# adc-dac.net
KiCad netlist of a schematic drawn in Altium Designer
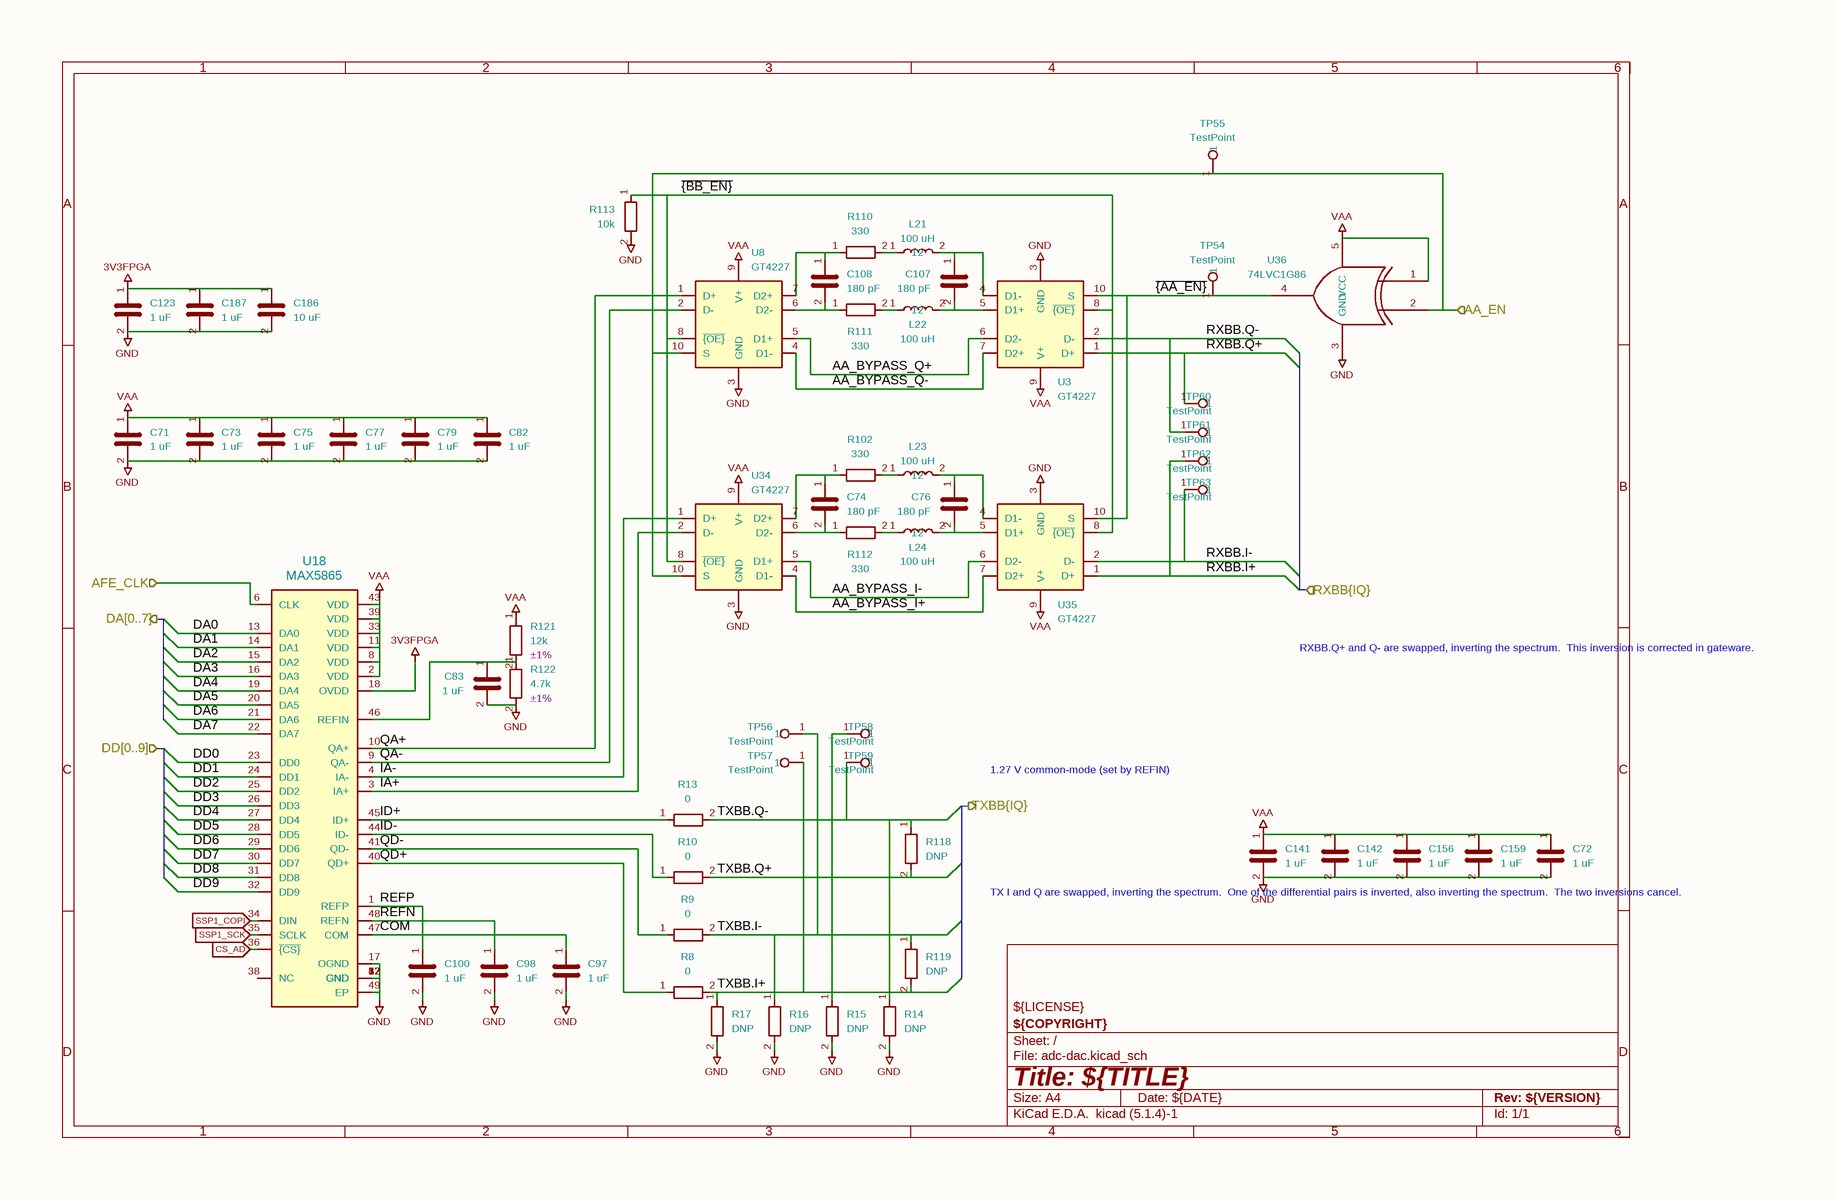
[diagram p0: adc-dac.SchDoc]

(export (version "E")
  (design (tool "Eeschema 10.0.6"))
  (components
    (comp (ref "C71")
      (value "1 uF")
      (footprint "C_0201_0603Metric")
      (description "CAP CER 1UF 10V X5R 0201")
      (fields (field (name "MANUFACTURER") "Murata") (field (name "PART NUMBER") "GRM033R61A105ME44D"))
      (libsource (lib "Device") (part "C"))
    )
    (comp (ref "C72")
      (value "1 uF")
      (footprint "C_0201_0603Metric")
      (description "CAP CER 1UF 10V X5R 0201")
      (fields (field (name "MANUFACTURER") "Murata") (field (name "PART NUMBER") "GRM033R61A105ME44D"))
      (libsource (lib "Device") (part "C"))
    )
    (comp (ref "C73")
      (value "1 uF")
      (footprint "C_0201_0603Metric")
      (description "CAP CER 1UF 10V X5R 0201")
      (fields (field (name "MANUFACTURER") "Murata") (field (name "PART NUMBER") "GRM033R61A105ME44D"))
      (libsource (lib "Device") (part "C"))
    )
    (comp (ref "C74")
      (value "180 pF")
      (footprint "C_0201_0603Metric")
      (description "CAP CER 180PF 50V C0G/NP0 0201")
      (fields (field (name "MANUFACTURER") "Murata") (field (name "PART NUMBER") "GRM0335C1H181JA01D"))
      (libsource (lib "Device") (part "C"))
    )
    (comp (ref "C75")
      (value "1 uF")
      (footprint "C_0201_0603Metric")
      (description "CAP CER 1UF 10V X5R 0201")
      (fields (field (name "MANUFACTURER") "Murata") (field (name "PART NUMBER") "GRM033R61A105ME44D"))
      (libsource (lib "Device") (part "C"))
    )
    (comp (ref "C76")
      (value "180 pF")
      (footprint "C_0201_0603Metric")
      (description "CAP CER 180PF 50V C0G/NP0 0201")
      (fields (field (name "MANUFACTURER") "Murata") (field (name "PART NUMBER") "GRM0335C1H181JA01D"))
      (libsource (lib "Device") (part "C"))
    )
    (comp (ref "C77")
      (value "1 uF")
      (footprint "C_0201_0603Metric")
      (description "CAP CER 1UF 10V X5R 0201")
      (fields (field (name "MANUFACTURER") "Murata") (field (name "PART NUMBER") "GRM033R61A105ME44D"))
      (libsource (lib "Device") (part "C"))
    )
    (comp (ref "C79")
      (value "1 uF")
      (footprint "C_0201_0603Metric")
      (description "CAP CER 1UF 10V X5R 0201")
      (fields (field (name "MANUFACTURER") "Murata") (field (name "PART NUMBER") "GRM033R61A105ME44D"))
      (libsource (lib "Device") (part "C"))
    )
    (comp (ref "C82")
      (value "1 uF")
      (footprint "C_0201_0603Metric")
      (description "CAP CER 1UF 10V X5R 0201")
      (fields (field (name "MANUFACTURER") "Murata") (field (name "PART NUMBER") "GRM033R61A105ME44D"))
      (libsource (lib "Device") (part "C"))
    )
    (comp (ref "C83")
      (value "1 uF")
      (footprint "C_0201_0603Metric")
      (description "CAP CER 1UF 10V X5R 0201")
      (fields (field (name "MANUFACTURER") "Murata") (field (name "PART NUMBER") "GRM033R61A105ME44D"))
      (libsource (lib "Device") (part "C"))
    )
    (comp (ref "C97")
      (value "1 uF")
      (footprint "C_0201_0603Metric")
      (description "CAP CER 1UF 10V X5R 0201")
      (fields (field (name "MANUFACTURER") "Murata") (field (name "PART NUMBER") "GRM033R61A105ME44D"))
      (libsource (lib "Device") (part "C"))
    )
    (comp (ref "C98")
      (value "1 uF")
      (footprint "C_0201_0603Metric")
      (description "CAP CER 1UF 10V X5R 0201")
      (fields (field (name "MANUFACTURER") "Murata") (field (name "PART NUMBER") "GRM033R61A105ME44D"))
      (libsource (lib "Device") (part "C"))
    )
    (comp (ref "C100")
      (value "1 uF")
      (footprint "C_0201_0603Metric")
      (description "CAP CER 1UF 10V X5R 0201")
      (fields (field (name "MANUFACTURER") "Murata") (field (name "PART NUMBER") "GRM033R61A105ME44D"))
      (libsource (lib "Device") (part "C"))
    )
    (comp (ref "C107")
      (value "180 pF")
      (footprint "C_0201_0603Metric")
      (description "CAP CER 180PF 50V C0G/NP0 0201")
      (fields (field (name "MANUFACTURER") "Murata") (field (name "PART NUMBER") "GRM0335C1H181JA01D"))
      (libsource (lib "Device") (part "C"))
    )
    (comp (ref "C108")
      (value "180 pF")
      (footprint "C_0201_0603Metric")
      (description "CAP CER 180PF 50V C0G/NP0 0201")
      (fields (field (name "MANUFACTURER") "Murata") (field (name "PART NUMBER") "GRM0335C1H181JA01D"))
      (libsource (lib "Device") (part "C"))
    )
    (comp (ref "C123")
      (value "1 uF")
      (footprint "C_0201_0603Metric")
      (description "CAP CER 1UF 10V X5R 0201")
      (fields (field (name "MANUFACTURER") "Murata") (field (name "PART NUMBER") "GRM033R61A105ME44D"))
      (libsource (lib "Device") (part "C"))
    )
    (comp (ref "C141")
      (value "1 uF")
      (footprint "C_0201_0603Metric")
      (description "CAP CER 1UF 10V X5R 0201")
      (fields (field (name "MANUFACTURER") "Murata") (field (name "PART NUMBER") "GRM033R61A105ME44D"))
      (libsource (lib "Device") (part "C"))
    )
    (comp (ref "C142")
      (value "1 uF")
      (footprint "C_0201_0603Metric")
      (description "CAP CER 1UF 10V X5R 0201")
      (fields (field (name "MANUFACTURER") "Murata") (field (name "PART NUMBER") "GRM033R61A105ME44D"))
      (libsource (lib "Device") (part "C"))
    )
    (comp (ref "C156")
      (value "1 uF")
      (footprint "C_0201_0603Metric")
      (description "CAP CER 1UF 10V X5R 0201")
      (fields (field (name "MANUFACTURER") "Murata") (field (name "PART NUMBER") "GRM033R61A105ME44D"))
      (libsource (lib "Device") (part "C"))
    )
    (comp (ref "C159")
      (value "1 uF")
      (footprint "C_0201_0603Metric")
      (description "CAP CER 1UF 10V X5R 0201")
      (fields (field (name "MANUFACTURER") "Murata") (field (name "PART NUMBER") "GRM033R61A105ME44D"))
      (libsource (lib "Device") (part "C"))
    )
    (comp (ref "C186")
      (value "10 uF")
      (footprint "C_0805_2012Metric")
      (description "CAP CER 10UF 16V X5R 0805")
      (fields (field (name "MANUFACTURER") "Samsung") (field (name "PART NUMBER") "CL21A106KOQNNNE"))
      (libsource (lib "Device") (part "C"))
    )
    (comp (ref "C187")
      (value "1 uF")
      (footprint "C_0201_0603Metric")
      (description "CAP CER 1UF 10V X5R 0201")
      (fields (field (name "MANUFACTURER") "Murata") (field (name "PART NUMBER") "GRM033R61A105ME44D"))
      (libsource (lib "Device") (part "C"))
    )
    (comp (ref "L21")
      (value "100 uH")
      (footprint "L_TDK_MLZ2012_h1.25mm")
      (description "FIXED IND 100UH 140MA 3.5OHM SMD")
      (fields (field (name "MANUFACTURER") "TDK") (field (name "PART NUMBER") "MLZ2012N101LT000"))
      (libsource (lib "Device") (part "L"))
    )
    (comp (ref "L22")
      (value "100 uH")
      (footprint "L_TDK_MLZ2012_h1.25mm")
      (description "FIXED IND 100UH 140MA 3.5OHM SMD")
      (fields (field (name "MANUFACTURER") "TDK") (field (name "PART NUMBER") "MLZ2012N101LT000"))
      (libsource (lib "Device") (part "L"))
    )
    (comp (ref "L23")
      (value "100 uH")
      (footprint "L_TDK_MLZ2012_h1.25mm")
      (description "FIXED IND 100UH 140MA 3.5OHM SMD")
      (fields (field (name "MANUFACTURER") "TDK") (field (name "PART NUMBER") "MLZ2012N101LT000"))
      (libsource (lib "Device") (part "L"))
    )
    (comp (ref "L24")
      (value "100 uH")
      (footprint "L_TDK_MLZ2012_h1.25mm")
      (description "FIXED IND 100UH 140MA 3.5OHM SMD")
      (fields (field (name "MANUFACTURER") "TDK") (field (name "PART NUMBER") "MLZ2012N101LT000"))
      (libsource (lib "Device") (part "L"))
    )
    (comp (ref "R8")
      (value "0")
      (footprint "R_0201_0603Metric")
      (description "RES 0 OHM JUMPER 1/20W 0201")
      (fields (field (name "MANUFACTURER") "Yageo") (field (name "PART NUMBER") "RC0201JR-070RL"))
      (libsource (lib "") (part "R_1"))
    )
    (comp (ref "R9")
      (value "0")
      (footprint "R_0201_0603Metric")
      (description "RES 0 OHM JUMPER 1/20W 0201")
      (fields (field (name "MANUFACTURER") "Yageo") (field (name "PART NUMBER") "RC0201JR-070RL"))
      (libsource (lib "") (part "R_1"))
    )
    (comp (ref "R10")
      (value "0")
      (footprint "R_0201_0603Metric")
      (description "RES 0 OHM JUMPER 1/20W 0201")
      (fields (field (name "MANUFACTURER") "Yageo") (field (name "PART NUMBER") "RC0201JR-070RL"))
      (libsource (lib "") (part "R_1"))
    )
    (comp (ref "R13")
      (value "0")
      (footprint "R_0201_0603Metric")
      (description "RES 0 OHM JUMPER 1/20W 0201")
      (fields (field (name "MANUFACTURER") "Yageo") (field (name "PART NUMBER") "RC0201JR-070RL"))
      (libsource (lib "") (part "R_1"))
    )
    (comp (ref "R14") (value "DNP") (footprint "R_0201_0603Metric") (libsource (lib "Device") (part "R")))
    (comp (ref "R15") (value "DNP") (footprint "R_0201_0603Metric") (libsource (lib "Device") (part "R")))
    (comp (ref "R16") (value "DNP") (footprint "R_0201_0603Metric") (libsource (lib "Device") (part "R")))
    (comp (ref "R17") (value "DNP") (footprint "R_0201_0603Metric") (libsource (lib "Device") (part "R")))
    (comp (ref "R102")
      (value "330")
      (footprint "R_0201_0603Metric")
      (description "RES 330 OHM 5% 1/20W 0201")
      (fields (field (name "MANUFACTURER") "Yageo") (field (name "PART NUMBER") "RC0201JR-07330RL"))
      (libsource (lib "") (part "R_1"))
    )
    (comp (ref "R110")
      (value "330")
      (footprint "R_0201_0603Metric")
      (description "RES 330 OHM 5% 1/20W 0201")
      (fields (field (name "MANUFACTURER") "Yageo") (field (name "PART NUMBER") "RC0201JR-07330RL"))
      (libsource (lib "") (part "R_1"))
    )
    (comp (ref "R111")
      (value "330")
      (footprint "R_0201_0603Metric")
      (description "RES 330 OHM 5% 1/20W 0201")
      (fields (field (name "MANUFACTURER") "Yageo") (field (name "PART NUMBER") "RC0201JR-07330RL"))
      (libsource (lib "") (part "R_1"))
    )
    (comp (ref "R112")
      (value "330")
      (footprint "R_0201_0603Metric")
      (description "RES 330 OHM 5% 1/20W 0201")
      (fields (field (name "MANUFACTURER") "Yageo") (field (name "PART NUMBER") "RC0201JR-07330RL"))
      (libsource (lib "") (part "R_1"))
    )
    (comp (ref "R113")
      (value "10k")
      (footprint "R_0402_1005Metric")
      (description "RES 10K OHM 1/16W 5% 0402 SMD")
      (fields (field (name "MANUFACTURER") "Yageo") (field (name "PART NUMBER") "RC0402JR-0710KL"))
      (libsource (lib "") (part "R_2"))
    )
    (comp (ref "R118") (value "DNP") (footprint "R_0201_0603Metric") (libsource (lib "Device") (part "R")))
    (comp (ref "R119") (value "DNP") (footprint "R_0201_0603Metric") (libsource (lib "Device") (part "R")))
    (comp (ref "R121")
      (value "12k")
      (footprint "R_0201_0603Metric")
      (description "RES 12K OHM 1% 1/20W 0201")
      (fields
        (field (name "MANUFACTURER") "Yageo")
        (field (name "PART NUMBER") "RC0201FR-0712KL")
        (field (name "TOLERANCE") "±1%")
      )
      (libsource (lib "") (part "R_2"))
    )
    (comp (ref "R122")
      (value "4.7k")
      (footprint "R_0201_0603Metric")
      (description "RES 4.7K OHM 1% 1/20W 0201")
      (fields
        (field (name "MANUFACTURER") "Yageo")
        (field (name "PART NUMBER") "RC0201FR-074K7L")
        (field (name "TOLERANCE") "±1%")
      )
      (libsource (lib "Device") (part "R"))
    )
    (comp (ref "TP54")
      (value "TestPoint")
      (footprint "TestPoint_Pad_D1.0mm")
      (libsource (lib "Connector") (part "TestPoint"))
    )
    (comp (ref "TP55")
      (value "TestPoint")
      (footprint "TestPoint_Pad_D1.0mm")
      (libsource (lib "Connector") (part "TestPoint"))
    )
    (comp (ref "TP56")
      (value "TestPoint")
      (footprint "TestPoint_Pad_D1.0mm")
      (libsource (lib "Connector") (part "TestPoint"))
    )
    (comp (ref "TP57")
      (value "TestPoint")
      (footprint "TestPoint_Pad_D1.0mm")
      (libsource (lib "Connector") (part "TestPoint"))
    )
    (comp (ref "TP58")
      (value "TestPoint")
      (footprint "TestPoint_Pad_D1.0mm")
      (libsource (lib "Connector") (part "TestPoint"))
    )
    (comp (ref "TP59")
      (value "TestPoint")
      (footprint "TestPoint_Pad_D1.0mm")
      (libsource (lib "Connector") (part "TestPoint"))
    )
    (comp (ref "TP60")
      (value "TestPoint")
      (footprint "TestPoint_Pad_D1.0mm")
      (libsource (lib "Connector") (part "TestPoint"))
    )
    (comp (ref "TP61")
      (value "TestPoint")
      (footprint "TestPoint_Pad_D1.0mm")
      (libsource (lib "Connector") (part "TestPoint"))
    )
    (comp (ref "TP62")
      (value "TestPoint")
      (footprint "TestPoint_Pad_D1.0mm")
      (libsource (lib "Connector") (part "TestPoint"))
    )
    (comp (ref "TP63")
      (value "TestPoint")
      (footprint "TestPoint_Pad_D1.0mm")
      (libsource (lib "Connector") (part "TestPoint"))
    )
    (comp (ref "U3")
      (value "GT4227")
      (footprint "GTIC_UQFN-10_1.4x1.8mm_P0.4mm")
      (description "USB 2.0 Switch with ESD Protection, UQFN-10 Pitch 0.4 mm")
      (fields (field (name "MANUFACTURER") "GTIC") (field (name "PART NUMBER") "GT4227QA"))
      (libsource (lib "") (part "GT4227QA_1"))
    )
    (comp (ref "U8")
      (value "GT4227")
      (footprint "GTIC_UQFN-10_1.4x1.8mm_P0.4mm")
      (description "USB 2.0 Switch with ESD Protection, UQFN-10 Pitch 0.4 mm")
      (fields (field (name "MANUFACTURER") "GTIC") (field (name "PART NUMBER") "GT4227QA"))
      (libsource (lib "praline") (part "GT4227QA"))
    )
    (comp (ref "U18")
      (value "MAX5865")
      (footprint "QFN-48-1EP_7x7mm_P0.5mm_EP5.3x5.3mm_ThermalVias")
      (description "IC ANLG FRONT END 40MSPS 48-TQFN")
      (fields (field (name "MANUFACTURER") "Maxim") (field (name "PART NUMBER") "MAX5865ETM+T"))
      (libsource (lib "praline") (part "MAX5864"))
    )
    (comp (ref "U34")
      (value "GT4227")
      (footprint "GTIC_UQFN-10_1.4x1.8mm_P0.4mm")
      (description "USB 2.0 Switch with ESD Protection, UQFN-10 Pitch 0.4 mm")
      (fields (field (name "MANUFACTURER") "GTIC") (field (name "PART NUMBER") "GT4227QA"))
      (libsource (lib "praline") (part "GT4227QA"))
    )
    (comp (ref "U35")
      (value "GT4227")
      (footprint "GTIC_UQFN-10_1.4x1.8mm_P0.4mm")
      (description "USB 2.0 Switch with ESD Protection, UQFN-10 Pitch 0.4 mm")
      (fields (field (name "MANUFACTURER") "GTIC") (field (name "PART NUMBER") "GT4227QA"))
      (libsource (lib "") (part "GT4227QA_1"))
    )
    (comp (ref "U36")
      (value "74LVC1G86")
      (footprint "SOT-353_SC-70-5")
      (description "IC GATE XOR 1CH 2-INP SC70-5")
      (fields (field (name "MANUFACTURER") "UMW") (field (name "PART NUMBER") "SN74LVC1G86DCKR"))
      (libsource (lib "74xGxx") (part "74LVC1G86"))
    )
  )
  (nets
    (net (code "3") (name "/AA_BYPASS_I+") (class "Default")
      (node (ref "U34") (pin "4") (pinfunction "D1-_4") (pintype "passive"))
      (node (ref "U35") (pin "7") (pinfunction "D2+_7") (pintype "passive"))
    )
    (net (code "4") (name "/AA_BYPASS_I-") (class "Default")
      (node (ref "U34") (pin "5") (pinfunction "D1+_5") (pintype "passive"))
      (node (ref "U35") (pin "6") (pinfunction "D2-_6") (pintype "passive"))
    )
    (net (code "5") (name "/AA_BYPASS_Q+") (class "Default")
      (node (ref "U3") (pin "6") (pinfunction "D2-_6") (pintype "passive"))
      (node (ref "U8") (pin "5") (pinfunction "D1+_5") (pintype "passive"))
    )
    (net (code "6") (name "/AA_BYPASS_Q-") (class "Default")
      (node (ref "U3") (pin "7") (pinfunction "D2+_7") (pintype "passive"))
      (node (ref "U8") (pin "4") (pinfunction "D1-_4") (pintype "passive"))
    )
    (net (code "7") (name "/AA_EN") (class "Default")
      (node (ref "TP55") (pin "1") (pinfunction "1_1") (pintype "passive"))
      (node (ref "U34") (pin "10") (pinfunction "S_10") (pintype "passive"))
      (node (ref "U36") (pin "2") (pinfunction "2_2") (pintype "passive"))
      (node (ref "U8") (pin "10") (pinfunction "S_10") (pintype "passive"))
    )
    (net (code "8") (name "/AFE_CLK") (class "Default")
      (node (ref "U18") (pin "6") (pinfunction "CLK_6") (pintype "passive"))
    )
    (net (code "9") (name "/COM") (class "Default")
      (node (ref "C97") (pin "1") (pinfunction "1_1") (pintype "passive"))
      (node (ref "U18") (pin "47") (pinfunction "COM_47") (pintype "passive"))
    )
    (net (code "10") (name "/CS_AD") (class "Default")
      (node (ref "U18") (pin "36") (pinfunction "~{{CS}}_36") (pintype "passive"))
    )
    (net (code "11") (name "/DA0") (class "Default")
      (node (ref "U18") (pin "13") (pinfunction "DA0_13") (pintype "passive"))
    )
    (net (code "12") (name "/DA1") (class "Default")
      (node (ref "U18") (pin "14") (pinfunction "DA1_14") (pintype "passive"))
    )
    (net (code "13") (name "/DA2") (class "Default")
      (node (ref "U18") (pin "15") (pinfunction "DA2_15") (pintype "passive"))
    )
    (net (code "14") (name "/DA3") (class "Default")
      (node (ref "U18") (pin "16") (pinfunction "DA3_16") (pintype "passive"))
    )
    (net (code "15") (name "/DA4") (class "Default")
      (node (ref "U18") (pin "19") (pinfunction "DA4_19") (pintype "passive"))
    )
    (net (code "16") (name "/DA5") (class "Default")
      (node (ref "U18") (pin "20") (pinfunction "DA5_20") (pintype "passive"))
    )
    (net (code "17") (name "/DA6") (class "Default")
      (node (ref "U18") (pin "21") (pinfunction "DA6_21") (pintype "passive"))
    )
    (net (code "18") (name "/DA7") (class "Default")
      (node (ref "U18") (pin "22") (pinfunction "DA7_22") (pintype "passive"))
    )
    (net (code "20") (name "/DD0") (class "Default")
      (node (ref "U18") (pin "23") (pinfunction "DD0_23") (pintype "passive"))
    )
    (net (code "21") (name "/DD1") (class "Default")
      (node (ref "U18") (pin "24") (pinfunction "DD1_24") (pintype "passive"))
    )
    (net (code "22") (name "/DD2") (class "Default")
      (node (ref "U18") (pin "25") (pinfunction "DD2_25") (pintype "passive"))
    )
    (net (code "23") (name "/DD3") (class "Default")
      (node (ref "U18") (pin "26") (pinfunction "DD3_26") (pintype "passive"))
    )
    (net (code "24") (name "/DD4") (class "Default")
      (node (ref "U18") (pin "27") (pinfunction "DD4_27") (pintype "passive"))
    )
    (net (code "25") (name "/DD5") (class "Default")
      (node (ref "U18") (pin "28") (pinfunction "DD5_28") (pintype "passive"))
    )
    (net (code "26") (name "/DD6") (class "Default")
      (node (ref "U18") (pin "29") (pinfunction "DD6_29") (pintype "passive"))
    )
    (net (code "27") (name "/DD7") (class "Default")
      (node (ref "U18") (pin "30") (pinfunction "DD7_30") (pintype "passive"))
    )
    (net (code "28") (name "/DD8") (class "Default")
      (node (ref "U18") (pin "31") (pinfunction "DD8_31") (pintype "passive"))
    )
    (net (code "29") (name "/DD9") (class "Default")
      (node (ref "U18") (pin "32") (pinfunction "DD9_32") (pintype "passive"))
    )
    (net (code "31") (name "/IA+") (class "Default")
      (node (ref "U18") (pin "3") (pinfunction "IA+_3") (pintype "passive"))
      (node (ref "U34") (pin "2") (pinfunction "D-_2") (pintype "passive"))
    )
    (net (code "32") (name "/IA-") (class "Default")
      (node (ref "U18") (pin "4") (pinfunction "IA-_4") (pintype "passive"))
      (node (ref "U34") (pin "1") (pinfunction "D+_1") (pintype "passive"))
    )
    (net (code "33") (name "/ID+") (class "Default")
      (node (ref "R13") (pin "1") (pinfunction "1_1") (pintype "passive"))
      (node (ref "U18") (pin "45") (pinfunction "ID+_45") (pintype "passive"))
    )
    (net (code "34") (name "/ID-") (class "Default")
      (node (ref "R10") (pin "1") (pinfunction "1_1") (pintype "passive"))
      (node (ref "U18") (pin "44") (pinfunction "ID-_44") (pintype "passive"))
    )
    (net (code "35") (name "/QA+") (class "Default")
      (node (ref "U18") (pin "10") (pinfunction "QA+_10") (pintype "passive"))
      (node (ref "U8") (pin "1") (pinfunction "D+_1") (pintype "passive"))
    )
    (net (code "36") (name "/QA-") (class "Default")
      (node (ref "U18") (pin "9") (pinfunction "QA-_9") (pintype "passive"))
      (node (ref "U8") (pin "2") (pinfunction "D-_2") (pintype "passive"))
    )
    (net (code "37") (name "/QD+") (class "Default")
      (node (ref "R8") (pin "1") (pinfunction "1_1") (pintype "passive"))
      (node (ref "U18") (pin "40") (pinfunction "QD+_40") (pintype "passive"))
    )
    (net (code "38") (name "/QD-") (class "Default")
      (node (ref "R9") (pin "1") (pinfunction "1_1") (pintype "passive"))
      (node (ref "U18") (pin "41") (pinfunction "QD-_41") (pintype "passive"))
    )
    (net (code "39") (name "/REFN") (class "Default")
      (node (ref "C98") (pin "1") (pinfunction "1_1") (pintype "passive"))
      (node (ref "U18") (pin "48") (pinfunction "REFN_48") (pintype "passive"))
    )
    (net (code "40") (name "/REFP") (class "Default")
      (node (ref "C100") (pin "1") (pinfunction "1_1") (pintype "passive"))
      (node (ref "U18") (pin "1") (pinfunction "REFP_1") (pintype "passive"))
    )
    (net (code "41") (name "/RXBB.I+") (class "Default")
      (node (ref "TP62") (pin "1") (pinfunction "1_1") (pintype "passive"))
      (node (ref "U35") (pin "1") (pinfunction "D+_1") (pintype "passive"))
    )
    (net (code "42") (name "/RXBB.I-") (class "Default")
      (node (ref "TP63") (pin "1") (pinfunction "1_1") (pintype "passive"))
      (node (ref "U35") (pin "2") (pinfunction "D-_2") (pintype "passive"))
    )
    (net (code "43") (name "/RXBB.Q+") (class "Default")
      (node (ref "TP60") (pin "1") (pinfunction "1_1") (pintype "passive"))
      (node (ref "U3") (pin "1") (pinfunction "D+_1") (pintype "passive"))
    )
    (net (code "44") (name "/RXBB.Q-") (class "Default")
      (node (ref "TP61") (pin "1") (pinfunction "1_1") (pintype "passive"))
      (node (ref "U3") (pin "2") (pinfunction "D-_2") (pintype "passive"))
    )
    (net (code "46") (name "/SSP1_COPI") (class "Default")
      (node (ref "U18") (pin "34") (pinfunction "DIN_34") (pintype "passive"))
    )
    (net (code "47") (name "/SSP1_SCK") (class "Default")
      (node (ref "U18") (pin "35") (pinfunction "SCLK_35") (pintype "passive"))
    )
    (net (code "48") (name "/TXBB.I+") (class "Default")
      (node (ref "R119") (pin "2") (pinfunction "2_2") (pintype "passive"))
      (node (ref "R17") (pin "1") (pinfunction "1_1") (pintype "passive"))
      (node (ref "R8") (pin "2") (pinfunction "2_2") (pintype "passive"))
      (node (ref "TP57") (pin "1") (pinfunction "1_1") (pintype "passive"))
    )
    (net (code "49") (name "/TXBB.I-") (class "Default")
      (node (ref "R119") (pin "1") (pinfunction "1_1") (pintype "passive"))
      (node (ref "R16") (pin "1") (pinfunction "1_1") (pintype "passive"))
      (node (ref "R9") (pin "2") (pinfunction "2_2") (pintype "passive"))
      (node (ref "TP56") (pin "1") (pinfunction "1_1") (pintype "passive"))
    )
    (net (code "50") (name "/TXBB.Q+") (class "Default")
      (node (ref "R10") (pin "2") (pinfunction "2_2") (pintype "passive"))
      (node (ref "R118") (pin "2") (pinfunction "2_2") (pintype "passive"))
      (node (ref "R15") (pin "1") (pinfunction "1_1") (pintype "passive"))
      (node (ref "TP58") (pin "1") (pinfunction "1_1") (pintype "passive"))
    )
    (net (code "51") (name "/TXBB.Q-") (class "Default")
      (node (ref "R118") (pin "1") (pinfunction "1_1") (pintype "passive"))
      (node (ref "R13") (pin "2") (pinfunction "2_2") (pintype "passive"))
      (node (ref "R14") (pin "1") (pinfunction "1_1") (pintype "passive"))
      (node (ref "TP59") (pin "1") (pinfunction "1_1") (pintype "passive"))
    )
    (net (code "53") (name "/~{{AA_EN}}") (class "Default")
      (node (ref "TP54") (pin "1") (pinfunction "1_1") (pintype "passive"))
      (node (ref "U3") (pin "10") (pinfunction "S_10") (pintype "passive"))
      (node (ref "U35") (pin "10") (pinfunction "S_10") (pintype "passive"))
      (node (ref "U36") (pin "4") (pinfunction "4_4") (pintype "passive"))
    )
    (net (code "54") (name "/~{{BB_EN}}") (class "Default")
      (node (ref "R113") (pin "1") (pinfunction "1_1") (pintype "passive"))
      (node (ref "U3") (pin "8") (pinfunction "~{{OE}}_8") (pintype "passive"))
      (node (ref "U34") (pin "8") (pinfunction "~{{OE}}_8") (pintype "passive"))
      (node (ref "U35") (pin "8") (pinfunction "~{{OE}}_8") (pintype "passive"))
      (node (ref "U8") (pin "8") (pinfunction "~{{OE}}_8") (pintype "passive"))
    )
    (net (code "55") (name "3V3FPGA") (class "Default")
      (node (ref "C123") (pin "1") (pinfunction "1_1") (pintype "passive"))
      (node (ref "C186") (pin "1") (pinfunction "1_1") (pintype "passive"))
      (node (ref "C187") (pin "1") (pinfunction "1_1") (pintype "passive"))
      (node (ref "U18") (pin "18") (pinfunction "OVDD_18") (pintype "passive"))
    )
    (net (code "56") (name "GND") (class "Default")
      (node (ref "C100") (pin "2") (pinfunction "2_2") (pintype "passive"))
      (node (ref "C123") (pin "2") (pinfunction "2_2") (pintype "passive"))
      (node (ref "C141") (pin "2") (pinfunction "2_2") (pintype "passive"))
      (node (ref "C142") (pin "2") (pinfunction "2_2") (pintype "passive"))
      (node (ref "C156") (pin "2") (pinfunction "2_2") (pintype "passive"))
      (node (ref "C159") (pin "2") (pinfunction "2_2") (pintype "passive"))
      (node (ref "C186") (pin "2") (pinfunction "2_2") (pintype "passive"))
      (node (ref "C187") (pin "2") (pinfunction "2_2") (pintype "passive"))
      (node (ref "C71") (pin "2") (pinfunction "2_2") (pintype "passive"))
      (node (ref "C72") (pin "2") (pinfunction "2_2") (pintype "passive"))
      (node (ref "C73") (pin "2") (pinfunction "2_2") (pintype "passive"))
      (node (ref "C75") (pin "2") (pinfunction "2_2") (pintype "passive"))
      (node (ref "C77") (pin "2") (pinfunction "2_2") (pintype "passive"))
      (node (ref "C79") (pin "2") (pinfunction "2_2") (pintype "passive"))
      (node (ref "C82") (pin "2") (pinfunction "2_2") (pintype "passive"))
      (node (ref "C83") (pin "2") (pinfunction "2_2") (pintype "passive"))
      (node (ref "C97") (pin "2") (pinfunction "2_2") (pintype "passive"))
      (node (ref "C98") (pin "2") (pinfunction "2_2") (pintype "passive"))
      (node (ref "R113") (pin "2") (pinfunction "2_2") (pintype "passive"))
      (node (ref "R122") (pin "2") (pinfunction "2_2") (pintype "passive"))
      (node (ref "R14") (pin "2") (pinfunction "2_2") (pintype "passive"))
      (node (ref "R15") (pin "2") (pinfunction "2_2") (pintype "passive"))
      (node (ref "R16") (pin "2") (pinfunction "2_2") (pintype "passive"))
      (node (ref "R17") (pin "2") (pinfunction "2_2") (pintype "passive"))
      (node (ref "U18") (pin "12") (pinfunction "GND_12") (pintype "passive"))
      (node (ref "U18") (pin "17") (pinfunction "OGND_17") (pintype "passive"))
      (node (ref "U18") (pin "37") (pinfunction "GND_37") (pintype "passive"))
      (node (ref "U18") (pin "42") (pinfunction "GND_42") (pintype "passive"))
      (node (ref "U18") (pin "49") (pinfunction "EP_49") (pintype "passive"))
      (node (ref "U18") (pin "5") (pinfunction "GND_5") (pintype "passive"))
      (node (ref "U18") (pin "7") (pinfunction "GND_7") (pintype "passive"))
      (node (ref "U3") (pin "3") (pinfunction "GND_3") (pintype "passive"))
      (node (ref "U34") (pin "3") (pinfunction "GND_3") (pintype "passive"))
      (node (ref "U35") (pin "3") (pinfunction "GND_3") (pintype "passive"))
      (node (ref "U36") (pin "3") (pinfunction "GND_3") (pintype "passive"))
      (node (ref "U8") (pin "3") (pinfunction "GND_3") (pintype "passive"))
    )
    (net (code "57") (name "Net-(L21-Pad1)") (class "Default")
      (node (ref "L21") (pin "1") (pinfunction "1_1") (pintype "passive"))
      (node (ref "R110") (pin "2") (pinfunction "2_2") (pintype "passive"))
    )
    (net (code "58") (name "Net-(L22-Pad1)") (class "Default")
      (node (ref "L22") (pin "1") (pinfunction "1_1") (pintype "passive"))
      (node (ref "R111") (pin "2") (pinfunction "2_2") (pintype "passive"))
    )
    (net (code "59") (name "Net-(L23-Pad1)") (class "Default")
      (node (ref "L23") (pin "1") (pinfunction "1_1") (pintype "passive"))
      (node (ref "R102") (pin "2") (pinfunction "2_2") (pintype "passive"))
    )
    (net (code "60") (name "Net-(L24-Pad1)") (class "Default")
      (node (ref "L24") (pin "1") (pinfunction "1_1") (pintype "passive"))
      (node (ref "R112") (pin "2") (pinfunction "2_2") (pintype "passive"))
    )
    (net (code "61") (name "Net-(U3-D1+)") (class "Default")
      (node (ref "C107") (pin "2") (pinfunction "2_2") (pintype "passive"))
      (node (ref "L22") (pin "2") (pinfunction "2_2") (pintype "passive"))
      (node (ref "U3") (pin "5") (pinfunction "D1+_5") (pintype "passive"))
    )
    (net (code "62") (name "Net-(U3-D1-)") (class "Default")
      (node (ref "C107") (pin "1") (pinfunction "1_1") (pintype "passive"))
      (node (ref "L21") (pin "2") (pinfunction "2_2") (pintype "passive"))
      (node (ref "U3") (pin "4") (pinfunction "D1-_4") (pintype "passive"))
    )
    (net (code "63") (name "Net-(U8-D2+)") (class "Default")
      (node (ref "C108") (pin "1") (pinfunction "1_1") (pintype "passive"))
      (node (ref "R110") (pin "1") (pinfunction "1_1") (pintype "passive"))
      (node (ref "U8") (pin "7") (pinfunction "D2+_7") (pintype "passive"))
    )
    (net (code "64") (name "Net-(U8-D2-)") (class "Default")
      (node (ref "C108") (pin "2") (pinfunction "2_2") (pintype "passive"))
      (node (ref "R111") (pin "1") (pinfunction "1_1") (pintype "passive"))
      (node (ref "U8") (pin "6") (pinfunction "D2-_6") (pintype "passive"))
    )
    (net (code "65") (name "Net-(U18-REFIN)") (class "Default")
      (node (ref "C83") (pin "1") (pinfunction "1_1") (pintype "passive"))
      (node (ref "R121") (pin "2") (pinfunction "2_2") (pintype "passive"))
      (node (ref "R122") (pin "1") (pinfunction "1_1") (pintype "passive"))
      (node (ref "U18") (pin "46") (pinfunction "REFIN_46") (pintype "passive"))
    )
    (net (code "66") (name "Net-(U34-D2+)") (class "Default")
      (node (ref "C74") (pin "1") (pinfunction "1_1") (pintype "passive"))
      (node (ref "R102") (pin "1") (pinfunction "1_1") (pintype "passive"))
      (node (ref "U34") (pin "7") (pinfunction "D2+_7") (pintype "passive"))
    )
    (net (code "67") (name "Net-(U34-D2-)") (class "Default")
      (node (ref "C74") (pin "2") (pinfunction "2_2") (pintype "passive"))
      (node (ref "R112") (pin "1") (pinfunction "1_1") (pintype "passive"))
      (node (ref "U34") (pin "6") (pinfunction "D2-_6") (pintype "passive"))
    )
    (net (code "68") (name "Net-(U35-D1+)") (class "Default")
      (node (ref "C76") (pin "2") (pinfunction "2_2") (pintype "passive"))
      (node (ref "L24") (pin "2") (pinfunction "2_2") (pintype "passive"))
      (node (ref "U35") (pin "5") (pinfunction "D1+_5") (pintype "passive"))
    )
    (net (code "69") (name "Net-(U35-D1-)") (class "Default")
      (node (ref "C76") (pin "1") (pinfunction "1_1") (pintype "passive"))
      (node (ref "L23") (pin "2") (pinfunction "2_2") (pintype "passive"))
      (node (ref "U35") (pin "4") (pinfunction "D1-_4") (pintype "passive"))
    )
    (net (code "70") (name "VAA") (class "Default")
      (node (ref "C141") (pin "1") (pinfunction "1_1") (pintype "passive"))
      (node (ref "C142") (pin "1") (pinfunction "1_1") (pintype "passive"))
      (node (ref "C156") (pin "1") (pinfunction "1_1") (pintype "passive"))
      (node (ref "C159") (pin "1") (pinfunction "1_1") (pintype "passive"))
      (node (ref "C71") (pin "1") (pinfunction "1_1") (pintype "passive"))
      (node (ref "C72") (pin "1") (pinfunction "1_1") (pintype "passive"))
      (node (ref "C73") (pin "1") (pinfunction "1_1") (pintype "passive"))
      (node (ref "C75") (pin "1") (pinfunction "1_1") (pintype "passive"))
      (node (ref "C77") (pin "1") (pinfunction "1_1") (pintype "passive"))
      (node (ref "C79") (pin "1") (pinfunction "1_1") (pintype "passive"))
      (node (ref "C82") (pin "1") (pinfunction "1_1") (pintype "passive"))
      (node (ref "R121") (pin "1") (pinfunction "1_1") (pintype "passive"))
      (node (ref "U18") (pin "11") (pinfunction "VDD_11") (pintype "passive"))
      (node (ref "U18") (pin "2") (pinfunction "VDD_2") (pintype "passive"))
      (node (ref "U18") (pin "33") (pinfunction "VDD_33") (pintype "passive"))
      (node (ref "U18") (pin "39") (pinfunction "VDD_39") (pintype "passive"))
      (node (ref "U18") (pin "43") (pinfunction "VDD_43") (pintype "passive"))
      (node (ref "U18") (pin "8") (pinfunction "VDD_8") (pintype "passive"))
      (node (ref "U3") (pin "9") (pinfunction "V+_9") (pintype "passive"))
      (node (ref "U34") (pin "9") (pinfunction "V+_9") (pintype "passive"))
      (node (ref "U35") (pin "9") (pinfunction "V+_9") (pintype "passive"))
      (node (ref "U36") (pin "1") (pinfunction "1_1") (pintype "passive"))
      (node (ref "U36") (pin "5") (pinfunction "VCC_5") (pintype "passive"))
      (node (ref "U8") (pin "9") (pinfunction "V+_9") (pintype "passive"))
    )
    (net (code "71") (name "unconnected-(U18-NC-Pad38)") (class "Default")
      (node (ref "U18") (pin "38") (pinfunction "NC_38") (pintype "passive"))
    )
  )
)
